# TUN7_Main.net
KiCad netlist of a schematic drawn in Altium Designer
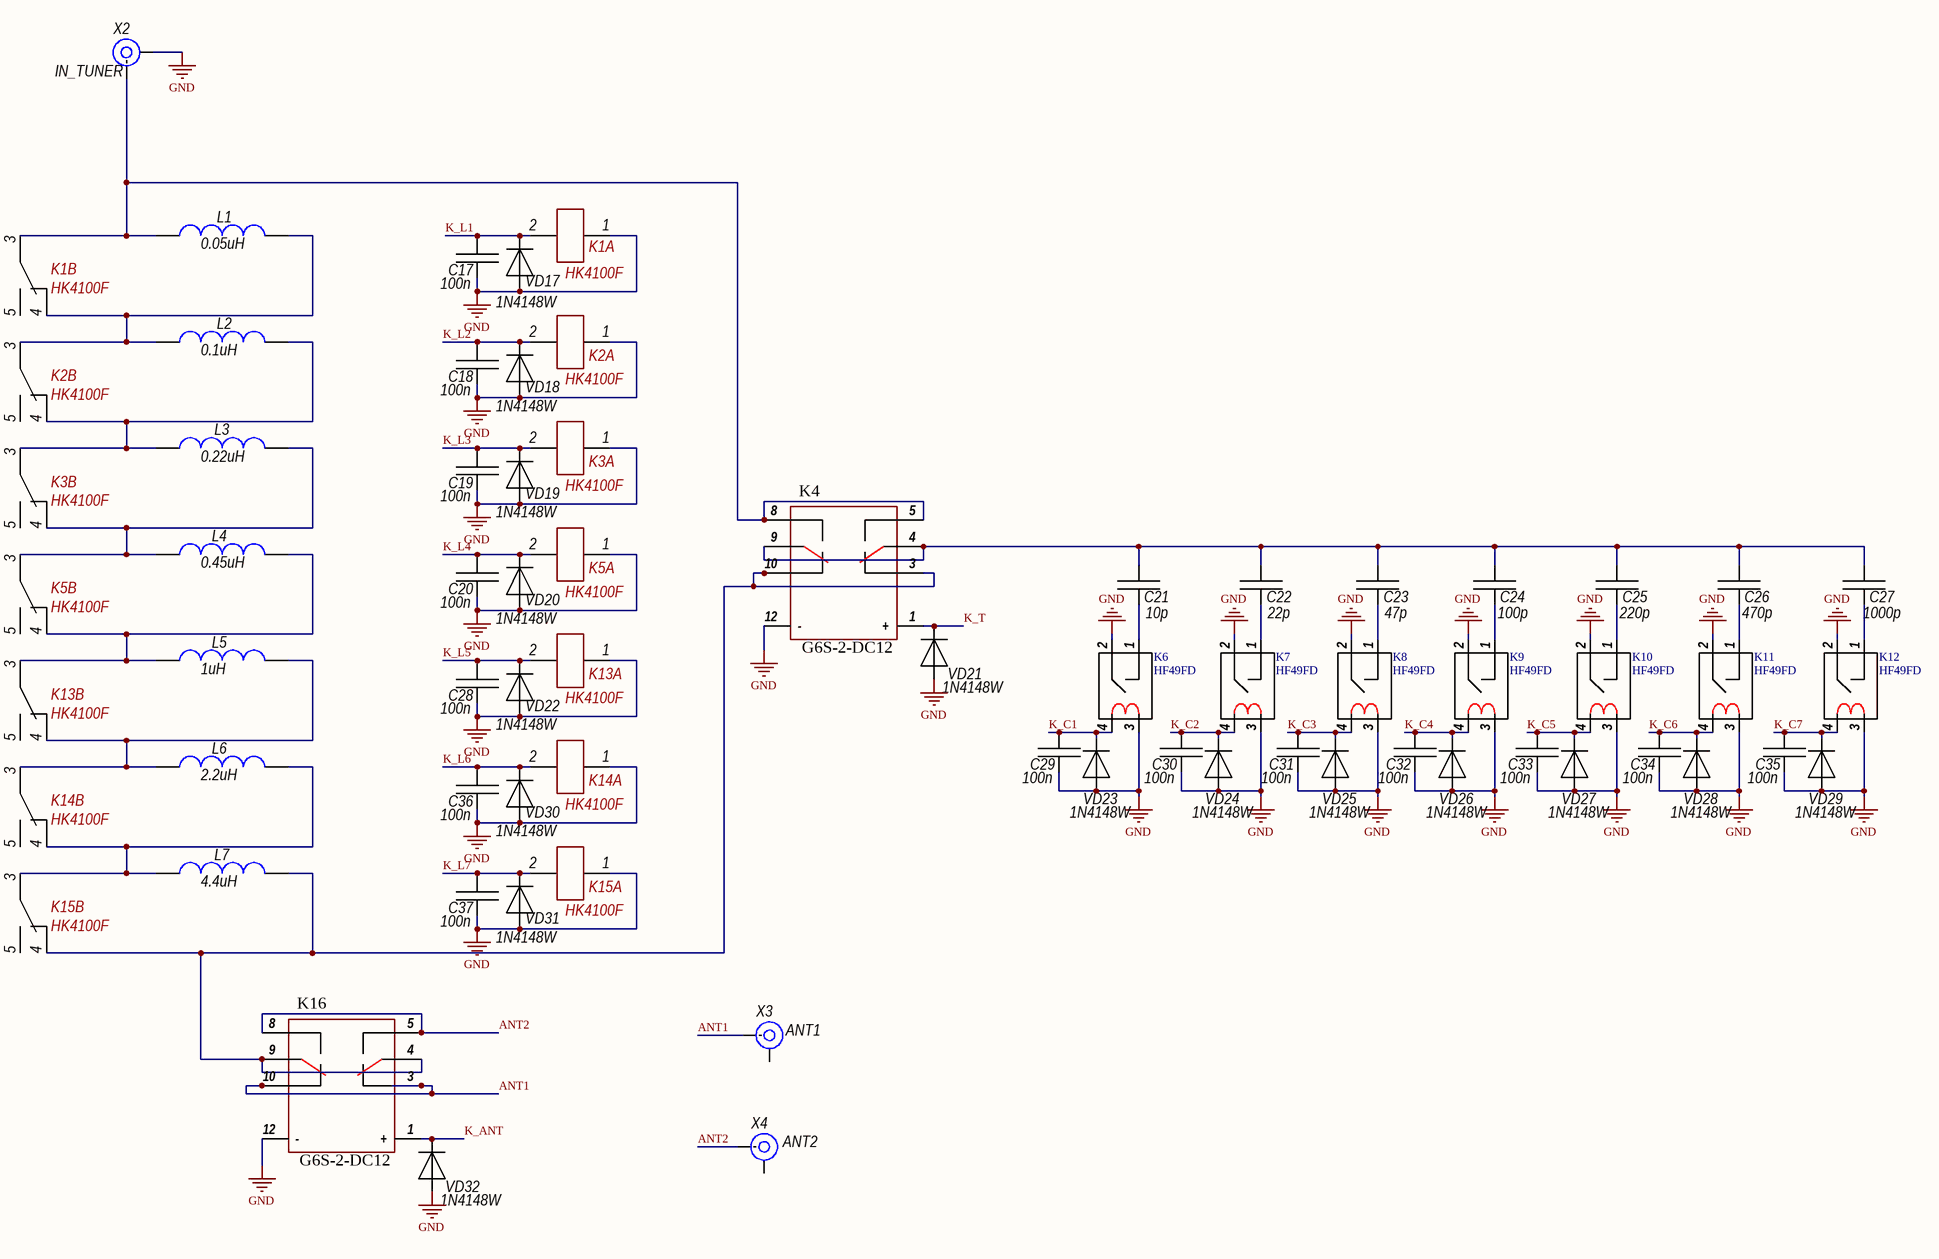
[diagram p0: TUN7_Main.SchDoc]

(export (version "E")
  (design (tool "Eeschema 10.0.6"))
  (components
    (comp (ref "C17")
      (value "100n")
      (footprint "standard:CH0805C")
      (libsource (lib "Discrete") (part "Capacitor"))
    )
    (comp (ref "C18")
      (value "100n")
      (footprint "standard:CH0805C")
      (libsource (lib "Discrete") (part "Capacitor"))
    )
    (comp (ref "C19")
      (value "100n")
      (footprint "standard:CH0805C")
      (libsource (lib "Discrete") (part "Capacitor"))
    )
    (comp (ref "C20")
      (value "100n")
      (footprint "standard:CH0805C")
      (libsource (lib "Discrete") (part "Capacitor"))
    )
    (comp (ref "C21") (value "10p") (footprint "CH1206ATC") (libsource (lib "Discrete") (part "Capacitor")))
    (comp (ref "C22") (value "22p") (footprint "CH1206ATC") (libsource (lib "Discrete") (part "Capacitor")))
    (comp (ref "C23") (value "47p") (footprint "CH1206ATC") (libsource (lib "Discrete") (part "Capacitor")))
    (comp (ref "C24") (value "100p") (footprint "CH1206ATC") (libsource (lib "Discrete") (part "Capacitor")))
    (comp (ref "C25") (value "220p") (footprint "CH1206ATC") (libsource (lib "Discrete") (part "Capacitor")))
    (comp (ref "C26") (value "470p") (footprint "CH1206ATC") (libsource (lib "Discrete") (part "Capacitor")))
    (comp (ref "C27") (value "1000p") (footprint "CH1206ATC") (libsource (lib "Discrete") (part "Capacitor")))
    (comp (ref "C28")
      (value "100n")
      (footprint "standard:CH0805C")
      (libsource (lib "Discrete") (part "Capacitor"))
    )
    (comp (ref "C29")
      (value "100n")
      (footprint "standard:CH0805C")
      (libsource (lib "Discrete") (part "Capacitor"))
    )
    (comp (ref "C30")
      (value "100n")
      (footprint "standard:CH0805C")
      (libsource (lib "Discrete") (part "Capacitor"))
    )
    (comp (ref "C31")
      (value "100n")
      (footprint "standard:CH0805C")
      (libsource (lib "Discrete") (part "Capacitor"))
    )
    (comp (ref "C32")
      (value "100n")
      (footprint "standard:CH0805C")
      (libsource (lib "Discrete") (part "Capacitor"))
    )
    (comp (ref "C33")
      (value "100n")
      (footprint "standard:CH0805C")
      (libsource (lib "Discrete") (part "Capacitor"))
    )
    (comp (ref "C34")
      (value "100n")
      (footprint "standard:CH0805C")
      (libsource (lib "Discrete") (part "Capacitor"))
    )
    (comp (ref "C35")
      (value "100n")
      (footprint "standard:CH0805C")
      (libsource (lib "Discrete") (part "Capacitor"))
    )
    (comp (ref "C36")
      (value "100n")
      (footprint "standard:CH0805C")
      (libsource (lib "Discrete") (part "Capacitor"))
    )
    (comp (ref "C37")
      (value "100n")
      (footprint "standard:CH0805C")
      (libsource (lib "Discrete") (part "Capacitor"))
    )
    (comp (ref "K1") (value "HK4100F") (footprint "NK4100F") (libsource (lib "") (part "NK4100F_1")))
    (comp (ref "K2") (value "HK4100F") (footprint "NK4100F") (libsource (lib "Relay") (part "NK4100F")))
    (comp (ref "K3") (value "HK4100F") (footprint "NK4100F") (libsource (lib "") (part "NK4100F_1")))
    (comp (ref "K4")
      (value "G6S-2-DC12")
      (footprint "G6S-2-DC12")
      (libsource (lib "Relay") (part "G6S-2-DC12V_2"))
    )
    (comp (ref "K5") (value "HK4100F") (footprint "NK4100F") (libsource (lib "") (part "NK4100F_1")))
    (comp (ref "K6") (value "HF49FD") (footprint "HF49FD") (libsource (lib "Relay") (part "HF49FD 012-1H12")))
    (comp (ref "K7") (value "HF49FD") (footprint "HF49FD") (libsource (lib "Relay") (part "HF49FD 012-1H12")))
    (comp (ref "K8") (value "HF49FD") (footprint "HF49FD") (libsource (lib "Relay") (part "HF49FD 012-1H12")))
    (comp (ref "K9") (value "HF49FD") (footprint "HF49FD") (libsource (lib "Relay") (part "HF49FD 012-1H12")))
    (comp (ref "K10")
      (value "HF49FD")
      (footprint "HF49FD")
      (libsource (lib "Relay") (part "HF49FD 012-1H12"))
    )
    (comp (ref "K11")
      (value "HF49FD")
      (footprint "HF49FD")
      (libsource (lib "Relay") (part "HF49FD 012-1H12"))
    )
    (comp (ref "K12")
      (value "HF49FD")
      (footprint "HF49FD")
      (libsource (lib "Relay") (part "HF49FD 012-1H12"))
    )
    (comp (ref "K13") (value "HK4100F") (footprint "NK4100F") (libsource (lib "Relay") (part "NK4100F")))
    (comp (ref "K14") (value "HK4100F") (footprint "NK4100F") (libsource (lib "") (part "NK4100F_1")))
    (comp (ref "K15") (value "HK4100F") (footprint "NK4100F") (libsource (lib "") (part "NK4100F_1")))
    (comp (ref "K16")
      (value "G6S-2-DC12")
      (footprint "G6S-2-DC12")
      (libsource (lib "Relay") (part "G6S-2-DC12V_2"))
    )
    (comp (ref "L1")
      (value "0.05uH")
      (footprint "DR1")
      (libsource (lib "Transformers") (part "Inductor ring"))
    )
    (comp (ref "L2")
      (value "0.1uH")
      (footprint "DR1")
      (libsource (lib "Transformers") (part "Inductor ring"))
    )
    (comp (ref "L3")
      (value "0.22uH")
      (footprint "DR1")
      (libsource (lib "Transformers") (part "Inductor ring"))
    )
    (comp (ref "L4")
      (value "0.45uH")
      (footprint "T68-0")
      (libsource (lib "Transformers") (part "Inductor ring"))
    )
    (comp (ref "L5")
      (value "1uH")
      (footprint "T68-0")
      (libsource (lib "Transformers") (part "Inductor ring"))
    )
    (comp (ref "L6")
      (value "2.2uH")
      (footprint "T68-0")
      (libsource (lib "Transformers") (part "Inductor ring"))
    )
    (comp (ref "L7")
      (value "4.4uH")
      (footprint "T68-0")
      (libsource (lib "Transformers") (part "Inductor ring"))
    )
    (comp (ref "VD17")
      (value "1N4148W")
      (footprint "standard:SOD123")
      (libsource (lib "Diods") (part "Diod"))
    )
    (comp (ref "VD18")
      (value "1N4148W")
      (footprint "standard:SOD123")
      (libsource (lib "Diods") (part "Diod"))
    )
    (comp (ref "VD19")
      (value "1N4148W")
      (footprint "standard:SOD123")
      (libsource (lib "Diods") (part "Diod"))
    )
    (comp (ref "VD20")
      (value "1N4148W")
      (footprint "standard:SOD123")
      (libsource (lib "Diods") (part "Diod"))
    )
    (comp (ref "VD21")
      (value "1N4148W")
      (footprint "standard:SOD123")
      (libsource (lib "Diods") (part "Diod"))
    )
    (comp (ref "VD22")
      (value "1N4148W")
      (footprint "standard:SOD123")
      (libsource (lib "Diods") (part "Diod"))
    )
    (comp (ref "VD23")
      (value "1N4148W")
      (footprint "standard:SOD123")
      (libsource (lib "Diods") (part "Diod"))
    )
    (comp (ref "VD24")
      (value "1N4148W")
      (footprint "standard:SOD123")
      (libsource (lib "Diods") (part "Diod"))
    )
    (comp (ref "VD25")
      (value "1N4148W")
      (footprint "standard:SOD123")
      (libsource (lib "Diods") (part "Diod"))
    )
    (comp (ref "VD26")
      (value "1N4148W")
      (footprint "standard:SOD123")
      (libsource (lib "Diods") (part "Diod"))
    )
    (comp (ref "VD27")
      (value "1N4148W")
      (footprint "standard:SOD123")
      (libsource (lib "Diods") (part "Diod"))
    )
    (comp (ref "VD28")
      (value "1N4148W")
      (footprint "standard:SOD123")
      (libsource (lib "Diods") (part "Diod"))
    )
    (comp (ref "VD29")
      (value "1N4148W")
      (footprint "standard:SOD123")
      (libsource (lib "Diods") (part "Diod"))
    )
    (comp (ref "VD30")
      (value "1N4148W")
      (footprint "standard:SOD123")
      (libsource (lib "Diods") (part "Diod"))
    )
    (comp (ref "VD31")
      (value "1N4148W")
      (footprint "standard:SOD123")
      (libsource (lib "Diods") (part "Diod"))
    )
    (comp (ref "VD32")
      (value "1N4148W")
      (footprint "standard:SOD123")
      (libsource (lib "Diods") (part "Diod"))
    )
    (comp (ref "X2")
      (value "IN_TUNER")
      (footprint "custom:CON: SMA")
      (description "RF")
      (libsource (lib "Connectors") (part "SMA"))
    )
    (comp (ref "X3")
      (value "ANT1")
      (footprint "custom:CON: SMA")
      (description "RF")
      (libsource (lib "Connectors") (part "SMA"))
    )
    (comp (ref "X4")
      (value "ANT2")
      (footprint "custom:CON: SMA")
      (description "RF")
      (libsource (lib "Connectors") (part "SMA"))
    )
  )
  (nets
    (net (code "1") (name "/ANT1") (class "Default")
      (node (ref "K16") (pin "10") (pinfunction "NC_2_10") (pintype "passive"))
      (node (ref "K16") (pin "3") (pinfunction "NC_1_3") (pintype "passive"))
      (node (ref "X3") (pin "1") (pinfunction "IN_1") (pintype "passive"))
    )
    (net (code "2") (name "/ANT2") (class "Default")
      (node (ref "K16") (pin "5") (pinfunction "NO_1_5") (pintype "passive"))
      (node (ref "K16") (pin "8") (pinfunction "NO_2_8") (pintype "passive"))
      (node (ref "X4") (pin "1") (pinfunction "IN_1") (pintype "passive"))
    )
    (net (code "3") (name "/K_ANT") (class "Default")
      (node (ref "K16") (pin "1") (pinfunction "+_1") (pintype "passive"))
      (node (ref "VD32") (pin "2") (pinfunction "2_2") (pintype "passive"))
    )
    (net (code "4") (name "/K_C1") (class "Default")
      (node (ref "C29") (pin "1") (pinfunction "1_1") (pintype "power_in"))
      (node (ref "K6") (pin "4") (pintype "passive"))
      (node (ref "VD23") (pin "2") (pinfunction "2_2") (pintype "passive"))
    )
    (net (code "5") (name "/K_C2") (class "Default")
      (node (ref "C30") (pin "1") (pinfunction "1_1") (pintype "power_in"))
      (node (ref "K7") (pin "4") (pintype "passive"))
      (node (ref "VD24") (pin "2") (pinfunction "2_2") (pintype "passive"))
    )
    (net (code "6") (name "/K_C3") (class "Default")
      (node (ref "C31") (pin "1") (pinfunction "1_1") (pintype "power_in"))
      (node (ref "K8") (pin "4") (pintype "passive"))
      (node (ref "VD25") (pin "2") (pinfunction "2_2") (pintype "passive"))
    )
    (net (code "7") (name "/K_C4") (class "Default")
      (node (ref "C32") (pin "1") (pinfunction "1_1") (pintype "power_in"))
      (node (ref "K9") (pin "4") (pintype "passive"))
      (node (ref "VD26") (pin "2") (pinfunction "2_2") (pintype "passive"))
    )
    (net (code "8") (name "/K_C5") (class "Default")
      (node (ref "C33") (pin "1") (pinfunction "1_1") (pintype "power_in"))
      (node (ref "K10") (pin "4") (pintype "passive"))
      (node (ref "VD27") (pin "2") (pinfunction "2_2") (pintype "passive"))
    )
    (net (code "9") (name "/K_C6") (class "Default")
      (node (ref "C34") (pin "1") (pinfunction "1_1") (pintype "power_in"))
      (node (ref "K11") (pin "4") (pintype "passive"))
      (node (ref "VD28") (pin "2") (pinfunction "2_2") (pintype "passive"))
    )
    (net (code "10") (name "/K_C7") (class "Default")
      (node (ref "C35") (pin "1") (pinfunction "1_1") (pintype "power_in"))
      (node (ref "K12") (pin "4") (pintype "passive"))
      (node (ref "VD29") (pin "2") (pinfunction "2_2") (pintype "passive"))
    )
    (net (code "11") (name "/K_L1") (class "Default")
      (node (ref "C17") (pin "1") (pinfunction "1_1") (pintype "power_in"))
      (node (ref "K1") (pin "2") (pinfunction "2_2") (pintype "passive"))
      (node (ref "VD17") (pin "2") (pinfunction "2_2") (pintype "passive"))
    )
    (net (code "12") (name "/K_L2") (class "Default")
      (node (ref "C18") (pin "1") (pinfunction "1_1") (pintype "power_in"))
      (node (ref "K2") (pin "2") (pinfunction "2_2") (pintype "passive"))
      (node (ref "VD18") (pin "2") (pinfunction "2_2") (pintype "passive"))
    )
    (net (code "13") (name "/K_L3") (class "Default")
      (node (ref "C19") (pin "1") (pinfunction "1_1") (pintype "power_in"))
      (node (ref "K3") (pin "2") (pinfunction "2_2") (pintype "passive"))
      (node (ref "VD19") (pin "2") (pinfunction "2_2") (pintype "passive"))
    )
    (net (code "14") (name "/K_L4") (class "Default")
      (node (ref "C20") (pin "1") (pinfunction "1_1") (pintype "power_in"))
      (node (ref "K5") (pin "2") (pinfunction "2_2") (pintype "passive"))
      (node (ref "VD20") (pin "2") (pinfunction "2_2") (pintype "passive"))
    )
    (net (code "15") (name "/K_L5") (class "Default")
      (node (ref "C28") (pin "1") (pinfunction "1_1") (pintype "power_in"))
      (node (ref "K13") (pin "2") (pinfunction "2_2") (pintype "passive"))
      (node (ref "VD22") (pin "2") (pinfunction "2_2") (pintype "passive"))
    )
    (net (code "16") (name "/K_L6") (class "Default")
      (node (ref "C36") (pin "1") (pinfunction "1_1") (pintype "power_in"))
      (node (ref "K14") (pin "2") (pinfunction "2_2") (pintype "passive"))
      (node (ref "VD30") (pin "2") (pinfunction "2_2") (pintype "passive"))
    )
    (net (code "17") (name "/K_L7") (class "Default")
      (node (ref "C37") (pin "1") (pinfunction "1_1") (pintype "power_in"))
      (node (ref "K15") (pin "2") (pinfunction "2_2") (pintype "passive"))
      (node (ref "VD31") (pin "2") (pinfunction "2_2") (pintype "passive"))
    )
    (net (code "18") (name "/K_T") (class "Default")
      (node (ref "K4") (pin "1") (pinfunction "+_1") (pintype "passive"))
      (node (ref "VD21") (pin "2") (pinfunction "2_2") (pintype "passive"))
    )
    (net (code "19") (name "GND") (class "Default")
      (node (ref "C17") (pin "2") (pinfunction "2_2") (pintype "power_in"))
      (node (ref "C18") (pin "2") (pinfunction "2_2") (pintype "power_in"))
      (node (ref "C19") (pin "2") (pinfunction "2_2") (pintype "power_in"))
      (node (ref "C20") (pin "2") (pinfunction "2_2") (pintype "power_in"))
      (node (ref "C28") (pin "2") (pinfunction "2_2") (pintype "power_in"))
      (node (ref "C29") (pin "2") (pinfunction "2_2") (pintype "power_in"))
      (node (ref "C30") (pin "2") (pinfunction "2_2") (pintype "power_in"))
      (node (ref "C31") (pin "2") (pinfunction "2_2") (pintype "power_in"))
      (node (ref "C32") (pin "2") (pinfunction "2_2") (pintype "power_in"))
      (node (ref "C33") (pin "2") (pinfunction "2_2") (pintype "power_in"))
      (node (ref "C34") (pin "2") (pinfunction "2_2") (pintype "power_in"))
      (node (ref "C35") (pin "2") (pinfunction "2_2") (pintype "power_in"))
      (node (ref "C36") (pin "2") (pinfunction "2_2") (pintype "power_in"))
      (node (ref "C37") (pin "2") (pinfunction "2_2") (pintype "power_in"))
      (node (ref "K1") (pin "1") (pinfunction "1_1") (pintype "passive"))
      (node (ref "K10") (pin "2") (pintype "passive"))
      (node (ref "K10") (pin "3") (pintype "passive"))
      (node (ref "K11") (pin "2") (pintype "passive"))
      (node (ref "K11") (pin "3") (pintype "passive"))
      (node (ref "K12") (pin "2") (pintype "passive"))
      (node (ref "K12") (pin "3") (pintype "passive"))
      (node (ref "K13") (pin "1") (pinfunction "1_1") (pintype "passive"))
      (node (ref "K14") (pin "1") (pinfunction "1_1") (pintype "passive"))
      (node (ref "K15") (pin "1") (pinfunction "1_1") (pintype "passive"))
      (node (ref "K16") (pin "12") (pinfunction "-_12") (pintype "passive"))
      (node (ref "K2") (pin "1") (pinfunction "1_1") (pintype "passive"))
      (node (ref "K3") (pin "1") (pinfunction "1_1") (pintype "passive"))
      (node (ref "K4") (pin "12") (pinfunction "-_12") (pintype "passive"))
      (node (ref "K5") (pin "1") (pinfunction "1_1") (pintype "passive"))
      (node (ref "K6") (pin "2") (pintype "passive"))
      (node (ref "K6") (pin "3") (pintype "passive"))
      (node (ref "K7") (pin "2") (pintype "passive"))
      (node (ref "K7") (pin "3") (pintype "passive"))
      (node (ref "K8") (pin "2") (pintype "passive"))
      (node (ref "K8") (pin "3") (pintype "passive"))
      (node (ref "K9") (pin "2") (pintype "passive"))
      (node (ref "K9") (pin "3") (pintype "passive"))
      (node (ref "VD17") (pin "1") (pinfunction "1_1") (pintype "passive"))
      (node (ref "VD18") (pin "1") (pinfunction "1_1") (pintype "passive"))
      (node (ref "VD19") (pin "1") (pinfunction "1_1") (pintype "passive"))
      (node (ref "VD20") (pin "1") (pinfunction "1_1") (pintype "passive"))
      (node (ref "VD21") (pin "1") (pinfunction "1_1") (pintype "passive"))
      (node (ref "VD22") (pin "1") (pinfunction "1_1") (pintype "passive"))
      (node (ref "VD23") (pin "1") (pinfunction "1_1") (pintype "passive"))
      (node (ref "VD24") (pin "1") (pinfunction "1_1") (pintype "passive"))
      (node (ref "VD25") (pin "1") (pinfunction "1_1") (pintype "passive"))
      (node (ref "VD26") (pin "1") (pinfunction "1_1") (pintype "passive"))
      (node (ref "VD27") (pin "1") (pinfunction "1_1") (pintype "passive"))
      (node (ref "VD28") (pin "1") (pinfunction "1_1") (pintype "passive"))
      (node (ref "VD29") (pin "1") (pinfunction "1_1") (pintype "passive"))
      (node (ref "VD30") (pin "1") (pinfunction "1_1") (pintype "passive"))
      (node (ref "VD31") (pin "1") (pinfunction "1_1") (pintype "passive"))
      (node (ref "VD32") (pin "1") (pinfunction "1_1") (pintype "passive"))
      (node (ref "X2") (pin "2") (pinfunction "IN_2") (pintype "passive"))
    )
    (net (code "20") (name "Net-(C21-Pad2)") (class "Default")
      (node (ref "C21") (pin "2") (pinfunction "2_2") (pintype "power_in"))
      (node (ref "K6") (pin "1") (pintype "passive"))
    )
    (net (code "21") (name "Net-(C22-Pad2)") (class "Default")
      (node (ref "C22") (pin "2") (pinfunction "2_2") (pintype "power_in"))
      (node (ref "K7") (pin "1") (pintype "passive"))
    )
    (net (code "22") (name "Net-(C23-Pad2)") (class "Default")
      (node (ref "C23") (pin "2") (pinfunction "2_2") (pintype "power_in"))
      (node (ref "K8") (pin "1") (pintype "passive"))
    )
    (net (code "23") (name "Net-(C24-Pad2)") (class "Default")
      (node (ref "C24") (pin "2") (pinfunction "2_2") (pintype "power_in"))
      (node (ref "K9") (pin "1") (pintype "passive"))
    )
    (net (code "24") (name "Net-(C25-Pad2)") (class "Default")
      (node (ref "C25") (pin "2") (pinfunction "2_2") (pintype "power_in"))
      (node (ref "K10") (pin "1") (pintype "passive"))
    )
    (net (code "25") (name "Net-(C26-Pad2)") (class "Default")
      (node (ref "C26") (pin "2") (pinfunction "2_2") (pintype "power_in"))
      (node (ref "K11") (pin "1") (pintype "passive"))
    )
    (net (code "26") (name "Net-(C27-Pad2)") (class "Default")
      (node (ref "C27") (pin "2") (pinfunction "2_2") (pintype "power_in"))
      (node (ref "K12") (pin "1") (pintype "passive"))
    )
    (net (code "27") (name "Net-(K1-Pad4)") (class "Default")
      (node (ref "K1") (pin "4") (pinfunction "4_4") (pintype "passive"))
      (node (ref "K2") (pin "3") (pinfunction "3_3") (pintype "passive"))
      (node (ref "L1") (pin "1") (pinfunction "1_1") (pintype "passive"))
      (node (ref "L2") (pin "2") (pinfunction "2_2") (pintype "passive"))
    )
    (net (code "28") (name "Net-(K2-Pad4)") (class "Default")
      (node (ref "K2") (pin "4") (pinfunction "4_4") (pintype "passive"))
      (node (ref "K3") (pin "3") (pinfunction "3_3") (pintype "passive"))
      (node (ref "L2") (pin "1") (pinfunction "1_1") (pintype "passive"))
      (node (ref "L3") (pin "2") (pinfunction "2_2") (pintype "passive"))
    )
    (net (code "29") (name "Net-(K3-Pad4)") (class "Default")
      (node (ref "K3") (pin "4") (pinfunction "4_4") (pintype "passive"))
      (node (ref "K5") (pin "3") (pinfunction "3_3") (pintype "passive"))
      (node (ref "L3") (pin "1") (pinfunction "1_1") (pintype "passive"))
      (node (ref "L4") (pin "2") (pinfunction "2_2") (pintype "passive"))
    )
    (net (code "30") (name "Net-(K4-COM_1)") (class "Default")
      (node (ref "C21") (pin "1") (pinfunction "1_1") (pintype "power_in"))
      (node (ref "C22") (pin "1") (pinfunction "1_1") (pintype "power_in"))
      (node (ref "C23") (pin "1") (pinfunction "1_1") (pintype "power_in"))
      (node (ref "C24") (pin "1") (pinfunction "1_1") (pintype "power_in"))
      (node (ref "C25") (pin "1") (pinfunction "1_1") (pintype "power_in"))
      (node (ref "C26") (pin "1") (pinfunction "1_1") (pintype "power_in"))
      (node (ref "C27") (pin "1") (pinfunction "1_1") (pintype "power_in"))
      (node (ref "K4") (pin "4") (pinfunction "COM_1_4") (pintype "passive"))
      (node (ref "K4") (pin "9") (pinfunction "COM_2_9") (pintype "passive"))
    )
    (net (code "31") (name "Net-(K4-NO_1)") (class "Default")
      (node (ref "K1") (pin "3") (pinfunction "3_3") (pintype "passive"))
      (node (ref "K4") (pin "5") (pinfunction "NO_1_5") (pintype "passive"))
      (node (ref "K4") (pin "8") (pinfunction "NO_2_8") (pintype "passive"))
      (node (ref "L1") (pin "2") (pinfunction "2_2") (pintype "passive"))
      (node (ref "X2") (pin "1") (pinfunction "IN_1") (pintype "passive"))
    )
    (net (code "32") (name "Net-(K13-Pad3)") (class "Default")
      (node (ref "K13") (pin "3") (pinfunction "3_3") (pintype "passive"))
      (node (ref "K5") (pin "4") (pinfunction "4_4") (pintype "passive"))
      (node (ref "L4") (pin "1") (pinfunction "1_1") (pintype "passive"))
      (node (ref "L5") (pin "2") (pinfunction "2_2") (pintype "passive"))
    )
    (net (code "33") (name "Net-(K13-Pad4)") (class "Default")
      (node (ref "K13") (pin "4") (pinfunction "4_4") (pintype "passive"))
      (node (ref "K14") (pin "3") (pinfunction "3_3") (pintype "passive"))
      (node (ref "L5") (pin "1") (pinfunction "1_1") (pintype "passive"))
      (node (ref "L6") (pin "2") (pinfunction "2_2") (pintype "passive"))
    )
    (net (code "34") (name "Net-(K14-Pad4)") (class "Default")
      (node (ref "K14") (pin "4") (pinfunction "4_4") (pintype "passive"))
      (node (ref "K15") (pin "3") (pinfunction "3_3") (pintype "passive"))
      (node (ref "L6") (pin "1") (pinfunction "1_1") (pintype "passive"))
      (node (ref "L7") (pin "2") (pinfunction "2_2") (pintype "passive"))
    )
    (net (code "35") (name "Net-(K16-COM_1)") (class "Default")
      (node (ref "K15") (pin "4") (pinfunction "4_4") (pintype "passive"))
      (node (ref "K16") (pin "4") (pinfunction "COM_1_4") (pintype "passive"))
      (node (ref "K16") (pin "9") (pinfunction "COM_2_9") (pintype "passive"))
      (node (ref "K4") (pin "10") (pinfunction "NC_2_10") (pintype "passive"))
      (node (ref "K4") (pin "3") (pinfunction "NC_1_3") (pintype "passive"))
      (node (ref "L7") (pin "1") (pinfunction "1_1") (pintype "passive"))
    )
    (net (code "36") (name "unconnected-(K1-Pad5)") (class "Default")
      (node (ref "K1") (pin "5") (pinfunction "5_5") (pintype "passive"))
    )
    (net (code "37") (name "unconnected-(K2-Pad5)") (class "Default")
      (node (ref "K2") (pin "5") (pinfunction "5_5") (pintype "passive"))
    )
    (net (code "38") (name "unconnected-(K3-Pad5)") (class "Default")
      (node (ref "K3") (pin "5") (pinfunction "5_5") (pintype "passive"))
    )
    (net (code "39") (name "unconnected-(K5-Pad5)") (class "Default")
      (node (ref "K5") (pin "5") (pinfunction "5_5") (pintype "passive"))
    )
    (net (code "40") (name "unconnected-(K13-Pad5)") (class "Default")
      (node (ref "K13") (pin "5") (pinfunction "5_5") (pintype "passive"))
    )
    (net (code "41") (name "unconnected-(K14-Pad5)") (class "Default")
      (node (ref "K14") (pin "5") (pinfunction "5_5") (pintype "passive"))
    )
    (net (code "42") (name "unconnected-(K15-Pad5)") (class "Default")
      (node (ref "K15") (pin "5") (pinfunction "5_5") (pintype "passive"))
    )
    (net (code "43") (name "unconnected-(X3-IN-Pad2)") (class "Default")
      (node (ref "X3") (pin "2") (pinfunction "IN_2") (pintype "passive"))
    )
    (net (code "44") (name "unconnected-(X4-IN-Pad2)") (class "Default")
      (node (ref "X4") (pin "2") (pinfunction "IN_2") (pintype "passive"))
    )
  )
)
